# BLE_Shield_v1_0.net
KiCad netlist of a schematic drawn in EAGLE
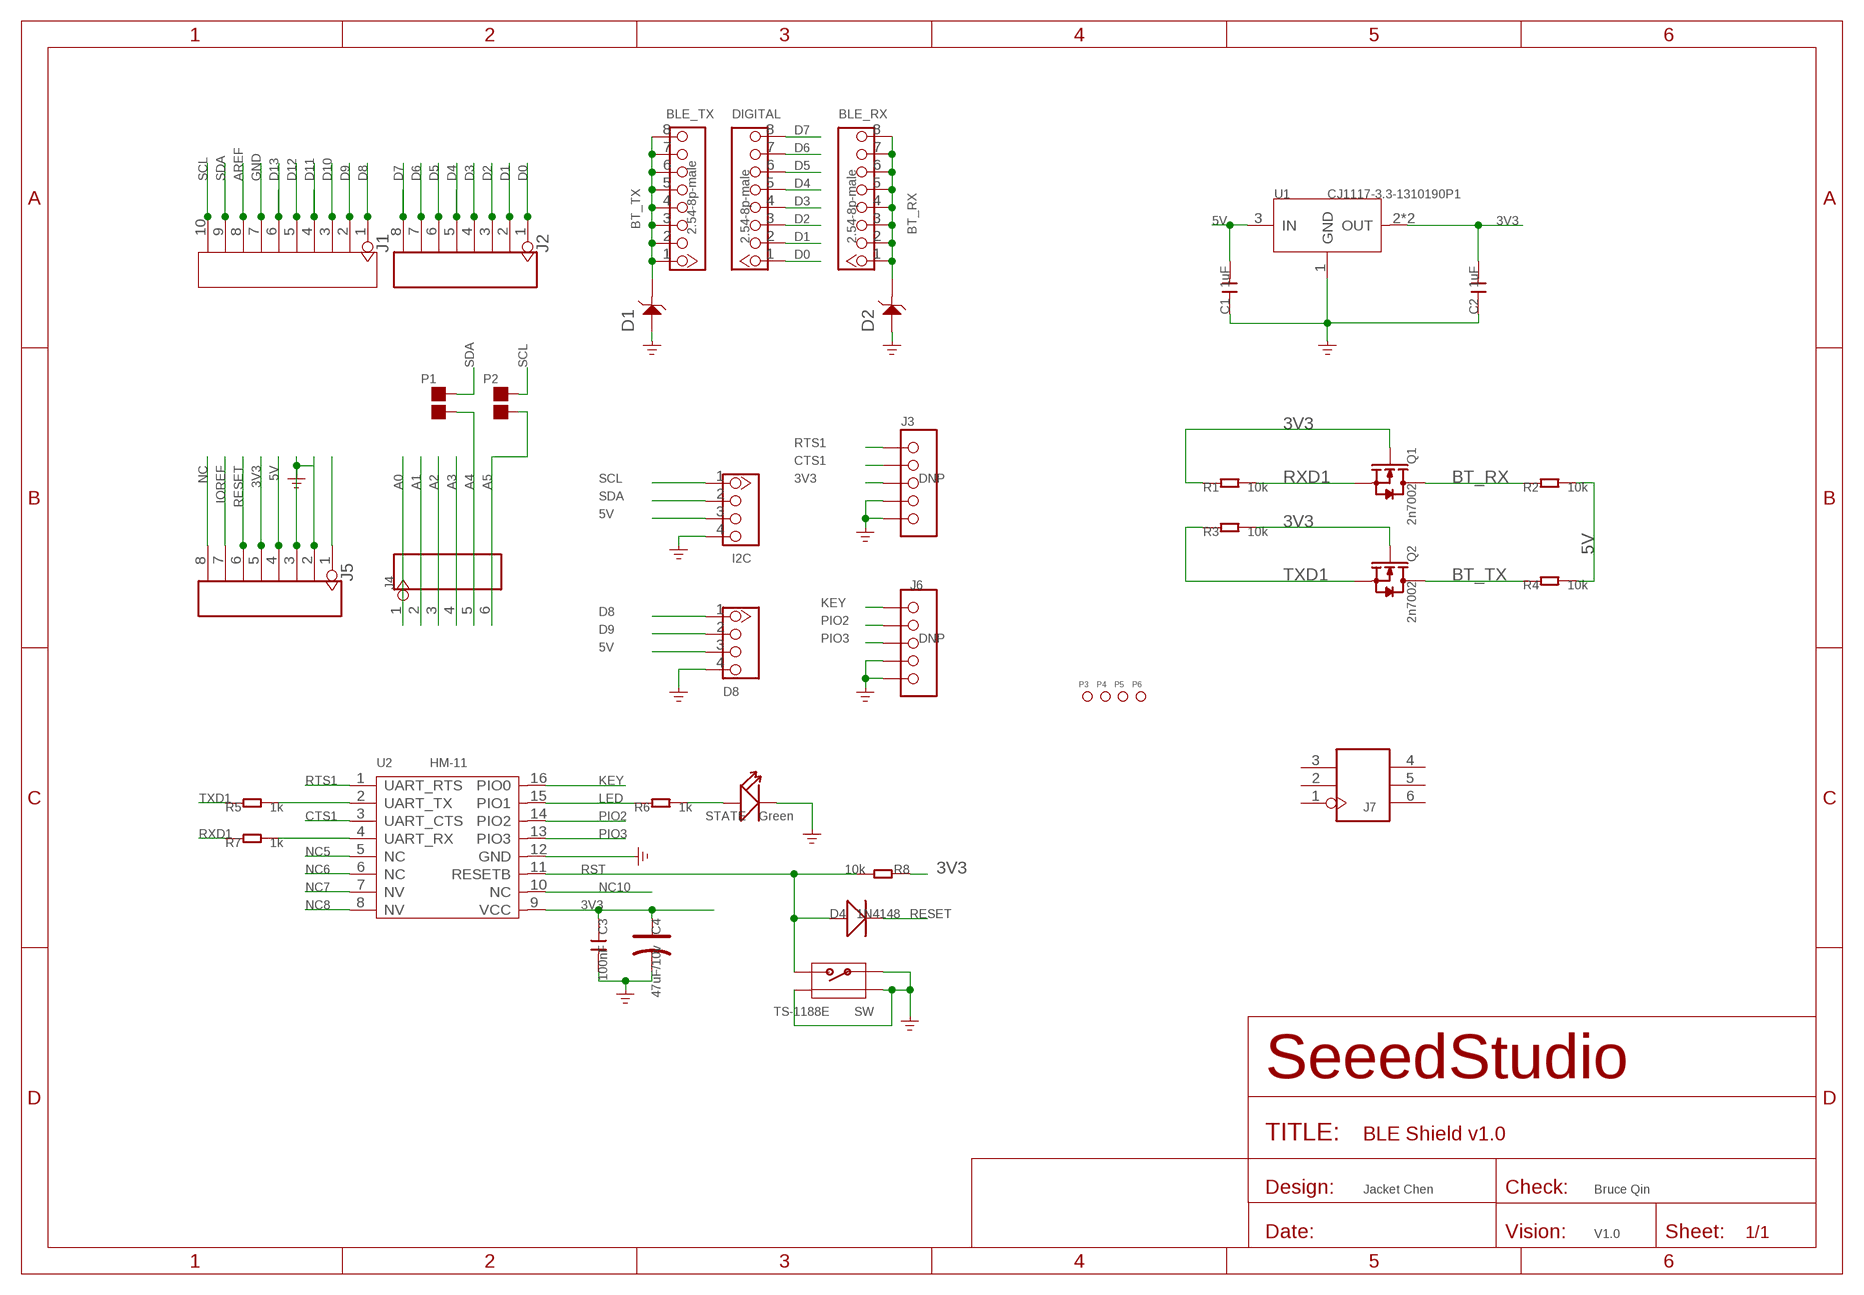
[diagram p0: schematic, sheet 1]

(export (version "E")
  (design (tool "Eeschema 10.0.6"))
  (components
    (comp (ref "BLE_RX")
      (value "2.54-8p-male")
      (footprint "eagle-import:8P-2.54")
      (libsource (lib "eagle-import") (part "HEADER-8P-2.54"))
    )
    (comp (ref "BLE_TX")
      (value "2.54-8p-male")
      (footprint "eagle-import:8P-2.54")
      (libsource (lib "eagle-import") (part "HEADER-8P-2.54"))
    )
    (comp (ref "C1")
      (value "1uF")
      (footprint "eagle-import:C0603")
      (libsource (lib "eagle-import") (part "C-0603"))
    )
    (comp (ref "C2")
      (value "1uF")
      (footprint "eagle-import:C0603")
      (libsource (lib "eagle-import") (part "C-0603"))
    )
    (comp (ref "C3")
      (value "100nF")
      (footprint "eagle-import:C0603")
      (libsource (lib "eagle-import") (part "C-0603"))
    )
    (comp (ref "C4")
      (value "47uF/10v")
      (footprint "eagle-import:AVX-A")
      (libsource (lib "eagle-import") (part "CAP-AVX-A"))
    )
    (comp (ref "D1")
      (value "6.2V/250mW")
      (footprint "eagle-import:SOD123-2.7X1.6")
      (libsource (lib "eagle-import") (part "D-ESD-2P'CESD5V0D1'"))
    )
    (comp (ref "D2")
      (value "6.2V/250mW")
      (footprint "eagle-import:SOD123-2.7X1.6")
      (libsource (lib "eagle-import") (part "D-ESD-2P'CESD5V0D1'"))
    )
    (comp (ref "D4")
      (value "1N4148")
      (footprint "eagle-import:LL-34")
      (libsource (lib "eagle-import") (part "D'1N4148-SMD'"))
    )
    (comp (ref "D8")
      (value "DIP Grove")
      (footprint "eagle-import:4P-2.0")
      (libsource (lib "eagle-import") (part "TWIG-4P-2.0-2.0"))
    )
    (comp (ref "DIGITAL")
      (value "2.54-8p-male")
      (footprint "eagle-import:8P-2.54")
      (libsource (lib "eagle-import") (part "HEADER-8P-2.54"))
    )
    (comp (ref "I2C")
      (value "DIP Grove")
      (footprint "eagle-import:4P-2.0")
      (libsource (lib "eagle-import") (part "TWIG-4P-2.0-2.0"))
    )
    (comp (ref "J1")
      (value "DIP Long Blue Female Header")
      (footprint "eagle-import:10P-2.54")
      (libsource (lib "eagle-import") (part "HEADER-10P-2.54"))
    )
    (comp (ref "J2")
      (value "DIP Long Blue Female Header")
      (footprint "eagle-import:8P-2.54-65_35MIL")
      (libsource (lib "eagle-import") (part "HEADER-8P-65/35MIL"))
    )
    (comp (ref "J3")
      (value "DNP")
      (footprint "eagle-import:5P-2.54")
      (libsource (lib "eagle-import") (part "HEADER-5P-2.54"))
    )
    (comp (ref "J4")
      (value "DIP Long Blue Female Header")
      (footprint "eagle-import:6P-2.54-65_35MIL")
      (libsource (lib "eagle-import") (part "HEADER-6P-65/35MIL"))
    )
    (comp (ref "J5")
      (value "DIP Long Blue Female Header")
      (footprint "eagle-import:8P-2.54-65_35MIL")
      (libsource (lib "eagle-import") (part "HEADER-8P-65/35MIL"))
    )
    (comp (ref "J6")
      (value "DNP")
      (footprint "eagle-import:5P-2.54")
      (libsource (lib "eagle-import") (part "HEADER-5P-2.54"))
    )
    (comp (ref "J7")
      (value "DIP Long Blue Female Header")
      (footprint "eagle-import:2X3P-2.54-65_35MIL")
      (libsource (lib "eagle-import") (part "HEADER-2X3P-65/35MIL"))
    )
    (comp (ref "P1")
      (value "DNP")
      (footprint "eagle-import:2P-SMD-1.78X1.27")
      (libsource (lib "eagle-import") (part "PAD-JUMPER-2P"))
    )
    (comp (ref "P2")
      (value "DNP")
      (footprint "eagle-import:2P-SMD-1.78X1.27")
      (libsource (lib "eagle-import") (part "PAD-JUMPER-2P"))
    )
    (comp (ref "P3")
      (value "PAD-MARK")
      (footprint "eagle-import:ROUND-MARK-1.0")
      (fields (field (name "PARTNO") "DNP"))
      (libsource (lib "eagle-import") (part "PAD-MARK"))
    )
    (comp (ref "P4")
      (value "PAD-MARK")
      (footprint "eagle-import:ROUND-MARK-1.0")
      (fields (field (name "PARTNO") "DNP"))
      (libsource (lib "eagle-import") (part "PAD-MARK"))
    )
    (comp (ref "P5")
      (value "PAD-MARK")
      (footprint "eagle-import:ROUND-MARK-1.0")
      (fields (field (name "PARTNO") "DNP"))
      (libsource (lib "eagle-import") (part "PAD-MARK"))
    )
    (comp (ref "P6")
      (value "PAD-MARK")
      (footprint "eagle-import:ROUND-MARK-1.0")
      (fields (field (name "PARTNO") "DNP"))
      (libsource (lib "eagle-import") (part "PAD-MARK"))
    )
    (comp (ref "Q1")
      (value "2n7002")
      (footprint "eagle-import:SOT23")
      (libsource (lib "eagle-import") (part "MOSFET-N'SOT23'"))
    )
    (comp (ref "Q2")
      (value "2n7002")
      (footprint "eagle-import:SOT23")
      (libsource (lib "eagle-import") (part "MOSFET-N'SOT23'"))
    )
    (comp (ref "R1")
      (value "10k")
      (footprint "eagle-import:R0603")
      (libsource (lib "eagle-import") (part "R-0603"))
    )
    (comp (ref "R2")
      (value "10k")
      (footprint "eagle-import:R0603")
      (libsource (lib "eagle-import") (part "R-0603"))
    )
    (comp (ref "R3")
      (value "10k")
      (footprint "eagle-import:R0603")
      (libsource (lib "eagle-import") (part "R-0603"))
    )
    (comp (ref "R4")
      (value "10k")
      (footprint "eagle-import:R0603")
      (libsource (lib "eagle-import") (part "R-0603"))
    )
    (comp (ref "R5")
      (value "1k")
      (footprint "eagle-import:R0603")
      (libsource (lib "eagle-import") (part "R-0603"))
    )
    (comp (ref "R6")
      (value "1k")
      (footprint "eagle-import:R0603")
      (libsource (lib "eagle-import") (part "R-0603"))
    )
    (comp (ref "R7")
      (value "1k")
      (footprint "eagle-import:R0603")
      (libsource (lib "eagle-import") (part "R-0603"))
    )
    (comp (ref "R8")
      (value "10k")
      (footprint "eagle-import:R0603")
      (libsource (lib "eagle-import") (part "R-0603"))
    )
    (comp (ref "STATE")
      (value "Green")
      (footprint "eagle-import:LED-0603")
      (libsource (lib "eagle-import") (part "LED'0603'"))
    )
    (comp (ref "SW")
      (value "TS-1188E")
      (footprint "eagle-import:4P-SMD-7X3.5X3.5H")
      (libsource (lib "eagle-import") (part "BUTTON-4P-REINFORCE'TS-1188E'"))
    )
    (comp (ref "U1")
      (value "CJ1117-3.3-1310190P1")
      (footprint "eagle-import:SOT223")
      (libsource (lib "eagle-import") (part "CJ1117-3.3-1310190P1"))
    )
    (comp (ref "U2")
      (value "HM-11")
      (footprint "eagle-import:16P-18.5X13.5X0.8")
      (libsource (lib "eagle-import") (part "HM-11"))
    )
  )
  (nets
    (net (code "1") (name "/3V3") (class "Default")
      (node (ref "C2") (pin "2") (pinfunction "2_2") (pintype "passive"))
      (node (ref "C3") (pin "1") (pinfunction "1_1") (pintype "passive"))
      (node (ref "C4") (pin "+") (pinfunction "+_+") (pintype "passive"))
      (node (ref "J3") (pin "3") (pinfunction "3_3") (pintype "bidirectional"))
      (node (ref "J5") (pin "5") (pinfunction "5_5") (pintype "bidirectional"))
      (node (ref "Q1") (pin "1") (pinfunction "G_1") (pintype "passive"))
      (node (ref "Q2") (pin "1") (pinfunction "G_1") (pintype "passive"))
      (node (ref "R1") (pin "1") (pinfunction "1_1") (pintype "passive"))
      (node (ref "R3") (pin "2") (pinfunction "2_2") (pintype "passive"))
      (node (ref "R8") (pin "1") (pinfunction "1_1") (pintype "passive"))
      (node (ref "U1") (pin "2") (pinfunction "OUT_2") (pintype "bidirectional"))
      (node (ref "U1") (pin "TER") (pinfunction "OUT_TER") (pintype "bidirectional"))
      (node (ref "U2") (pin "9") (pinfunction "VCC_9") (pintype "bidirectional"))
    )
    (net (code "2") (name "/5V") (class "Default")
      (node (ref "C1") (pin "2") (pinfunction "2_2") (pintype "passive"))
      (node (ref "D8") (pin "3") (pinfunction "3_3") (pintype "bidirectional"))
      (node (ref "I2C") (pin "3") (pinfunction "3_3") (pintype "bidirectional"))
      (node (ref "J5") (pin "4") (pinfunction "4_4") (pintype "bidirectional"))
      (node (ref "R2") (pin "2") (pinfunction "2_2") (pintype "passive"))
      (node (ref "R4") (pin "2") (pinfunction "2_2") (pintype "passive"))
      (node (ref "U1") (pin "3") (pinfunction "IN_3") (pintype "bidirectional"))
    )
    (net (code "3") (name "/A0") (class "Default")
      (node (ref "J4") (pin "1") (pinfunction "1_1") (pintype "bidirectional"))
    )
    (net (code "4") (name "/A1") (class "Default")
      (node (ref "J4") (pin "2") (pinfunction "2_2") (pintype "bidirectional"))
    )
    (net (code "5") (name "/A2") (class "Default")
      (node (ref "J4") (pin "3") (pinfunction "3_3") (pintype "bidirectional"))
    )
    (net (code "6") (name "/A3") (class "Default")
      (node (ref "J4") (pin "4") (pinfunction "4_4") (pintype "bidirectional"))
    )
    (net (code "7") (name "/A4") (class "Default")
      (node (ref "J4") (pin "5") (pinfunction "5_5") (pintype "bidirectional"))
      (node (ref "P1") (pin "1") (pinfunction "1_1") (pintype "bidirectional"))
    )
    (net (code "8") (name "/A5") (class "Default")
      (node (ref "J4") (pin "6") (pinfunction "6_6") (pintype "bidirectional"))
      (node (ref "P2") (pin "1") (pinfunction "1_1") (pintype "bidirectional"))
    )
    (net (code "9") (name "/AREF") (class "Default")
      (node (ref "J1") (pin "8") (pinfunction "8_8") (pintype "bidirectional"))
    )
    (net (code "10") (name "/BT_RX") (class "Default")
      (node (ref "BLE_RX") (pin "1") (pinfunction "1_1") (pintype "bidirectional"))
      (node (ref "BLE_RX") (pin "2") (pinfunction "2_2") (pintype "bidirectional"))
      (node (ref "BLE_RX") (pin "3") (pinfunction "3_3") (pintype "bidirectional"))
      (node (ref "BLE_RX") (pin "4") (pinfunction "4_4") (pintype "bidirectional"))
      (node (ref "BLE_RX") (pin "5") (pinfunction "5_5") (pintype "bidirectional"))
      (node (ref "BLE_RX") (pin "6") (pinfunction "6_6") (pintype "bidirectional"))
      (node (ref "BLE_RX") (pin "7") (pinfunction "7_7") (pintype "bidirectional"))
      (node (ref "BLE_RX") (pin "8") (pinfunction "8_8") (pintype "bidirectional"))
      (node (ref "D2") (pin "2") (pinfunction "2_2") (pintype "bidirectional"))
      (node (ref "Q1") (pin "3") (pinfunction "D_3") (pintype "passive"))
      (node (ref "R2") (pin "1") (pinfunction "1_1") (pintype "passive"))
    )
    (net (code "11") (name "/BT_TX") (class "Default")
      (node (ref "BLE_TX") (pin "1") (pinfunction "1_1") (pintype "bidirectional"))
      (node (ref "BLE_TX") (pin "2") (pinfunction "2_2") (pintype "bidirectional"))
      (node (ref "BLE_TX") (pin "3") (pinfunction "3_3") (pintype "bidirectional"))
      (node (ref "BLE_TX") (pin "4") (pinfunction "4_4") (pintype "bidirectional"))
      (node (ref "BLE_TX") (pin "5") (pinfunction "5_5") (pintype "bidirectional"))
      (node (ref "BLE_TX") (pin "6") (pinfunction "6_6") (pintype "bidirectional"))
      (node (ref "BLE_TX") (pin "7") (pinfunction "7_7") (pintype "bidirectional"))
      (node (ref "BLE_TX") (pin "8") (pinfunction "8_8") (pintype "bidirectional"))
      (node (ref "D1") (pin "2") (pinfunction "2_2") (pintype "bidirectional"))
      (node (ref "Q2") (pin "3") (pinfunction "D_3") (pintype "passive"))
      (node (ref "R4") (pin "1") (pinfunction "1_1") (pintype "passive"))
    )
    (net (code "12") (name "/CTS1") (class "Default")
      (node (ref "J3") (pin "2") (pinfunction "2_2") (pintype "bidirectional"))
      (node (ref "U2") (pin "3") (pinfunction "UART_CTS_3") (pintype "bidirectional"))
    )
    (net (code "13") (name "/D0") (class "Default")
      (node (ref "DIGITAL") (pin "1") (pinfunction "1_1") (pintype "bidirectional"))
      (node (ref "J2") (pin "1") (pinfunction "1_1") (pintype "bidirectional"))
    )
    (net (code "14") (name "/D1") (class "Default")
      (node (ref "DIGITAL") (pin "2") (pinfunction "2_2") (pintype "bidirectional"))
      (node (ref "J2") (pin "2") (pinfunction "2_2") (pintype "bidirectional"))
    )
    (net (code "15") (name "/D2") (class "Default")
      (node (ref "DIGITAL") (pin "3") (pinfunction "3_3") (pintype "bidirectional"))
      (node (ref "J2") (pin "3") (pinfunction "3_3") (pintype "bidirectional"))
    )
    (net (code "16") (name "/D3") (class "Default")
      (node (ref "DIGITAL") (pin "4") (pinfunction "4_4") (pintype "bidirectional"))
      (node (ref "J2") (pin "4") (pinfunction "4_4") (pintype "bidirectional"))
    )
    (net (code "17") (name "/D4") (class "Default")
      (node (ref "DIGITAL") (pin "5") (pinfunction "5_5") (pintype "bidirectional"))
      (node (ref "J2") (pin "5") (pinfunction "5_5") (pintype "bidirectional"))
    )
    (net (code "18") (name "/D5") (class "Default")
      (node (ref "DIGITAL") (pin "6") (pinfunction "6_6") (pintype "bidirectional"))
      (node (ref "J2") (pin "6") (pinfunction "6_6") (pintype "bidirectional"))
    )
    (net (code "19") (name "/D6") (class "Default")
      (node (ref "DIGITAL") (pin "7") (pinfunction "7_7") (pintype "bidirectional"))
      (node (ref "J2") (pin "7") (pinfunction "7_7") (pintype "bidirectional"))
    )
    (net (code "20") (name "/D7") (class "Default")
      (node (ref "DIGITAL") (pin "8") (pinfunction "8_8") (pintype "bidirectional"))
      (node (ref "J2") (pin "8") (pinfunction "8_8") (pintype "bidirectional"))
    )
    (net (code "21") (name "/D8") (class "Default")
      (node (ref "D8") (pin "1") (pinfunction "1_1") (pintype "bidirectional"))
      (node (ref "J1") (pin "1") (pinfunction "1_1") (pintype "bidirectional"))
    )
    (net (code "22") (name "/D9") (class "Default")
      (node (ref "D8") (pin "2") (pinfunction "2_2") (pintype "bidirectional"))
      (node (ref "J1") (pin "2") (pinfunction "2_2") (pintype "bidirectional"))
    )
    (net (code "23") (name "/D10") (class "Default")
      (node (ref "J1") (pin "3") (pinfunction "3_3") (pintype "bidirectional"))
    )
    (net (code "24") (name "/D11") (class "Default")
      (node (ref "J1") (pin "4") (pinfunction "4_4") (pintype "bidirectional"))
    )
    (net (code "25") (name "/D12") (class "Default")
      (node (ref "J1") (pin "5") (pinfunction "5_5") (pintype "bidirectional"))
    )
    (net (code "26") (name "/D13") (class "Default")
      (node (ref "J1") (pin "6") (pinfunction "6_6") (pintype "bidirectional"))
    )
    (net (code "27") (name "/IOREF") (class "Default")
      (node (ref "J5") (pin "7") (pinfunction "7_7") (pintype "bidirectional"))
    )
    (net (code "28") (name "/KEY") (class "Default")
      (node (ref "J6") (pin "1") (pinfunction "1_1") (pintype "bidirectional"))
      (node (ref "U2") (pin "16") (pinfunction "PIO0_16") (pintype "bidirectional"))
    )
    (net (code "29") (name "/LED") (class "Default")
      (node (ref "R6") (pin "1") (pinfunction "1_1") (pintype "passive"))
      (node (ref "U2") (pin "15") (pinfunction "PIO1_15") (pintype "bidirectional"))
    )
    (net (code "30") (name "/NC") (class "Default")
      (node (ref "J5") (pin "8") (pinfunction "8_8") (pintype "bidirectional"))
    )
    (net (code "31") (name "/NC5") (class "Default")
      (node (ref "U2") (pin "5") (pinfunction "NC_5") (pintype "bidirectional"))
    )
    (net (code "32") (name "/NC6") (class "Default")
      (node (ref "U2") (pin "6") (pinfunction "NC_6") (pintype "bidirectional"))
    )
    (net (code "33") (name "/NC7") (class "Default")
      (node (ref "U2") (pin "7") (pinfunction "NV_7") (pintype "bidirectional"))
    )
    (net (code "34") (name "/NC8") (class "Default")
      (node (ref "U2") (pin "8") (pinfunction "NV_8") (pintype "bidirectional"))
    )
    (net (code "35") (name "/NC10") (class "Default")
      (node (ref "U2") (pin "10") (pinfunction "NC_10") (pintype "bidirectional"))
    )
    (net (code "36") (name "/PIO2") (class "Default")
      (node (ref "J6") (pin "2") (pinfunction "2_2") (pintype "bidirectional"))
      (node (ref "U2") (pin "14") (pinfunction "PIO2_14") (pintype "bidirectional"))
    )
    (net (code "37") (name "/PIO3") (class "Default")
      (node (ref "J6") (pin "3") (pinfunction "3_3") (pintype "bidirectional"))
      (node (ref "U2") (pin "13") (pinfunction "PIO3_13") (pintype "bidirectional"))
    )
    (net (code "38") (name "/RESET") (class "Default")
      (node (ref "D4") (pin "C") (pinfunction "-_C") (pintype "passive"))
      (node (ref "J5") (pin "6") (pinfunction "6_6") (pintype "bidirectional"))
    )
    (net (code "39") (name "/RST") (class "Default")
      (node (ref "D4") (pin "A") (pinfunction "+_A") (pintype "passive"))
      (node (ref "R8") (pin "2") (pinfunction "2_2") (pintype "passive"))
      (node (ref "SW") (pin "2") (pinfunction "2_2") (pintype "bidirectional"))
      (node (ref "U2") (pin "11") (pinfunction "RESETB_11") (pintype "bidirectional"))
    )
    (net (code "40") (name "/RTS1") (class "Default")
      (node (ref "J3") (pin "1") (pinfunction "1_1") (pintype "bidirectional"))
      (node (ref "U2") (pin "1") (pinfunction "UART_RTS_1") (pintype "bidirectional"))
    )
    (net (code "41") (name "/RXD1") (class "Default")
      (node (ref "Q1") (pin "2") (pinfunction "S_2") (pintype "passive"))
      (node (ref "R1") (pin "2") (pinfunction "2_2") (pintype "passive"))
      (node (ref "R7") (pin "1") (pinfunction "1_1") (pintype "passive"))
    )
    (net (code "42") (name "/SCL") (class "Default")
      (node (ref "I2C") (pin "1") (pinfunction "1_1") (pintype "bidirectional"))
      (node (ref "J1") (pin "10") (pinfunction "10_10") (pintype "bidirectional"))
      (node (ref "P2") (pin "2") (pinfunction "2_2") (pintype "bidirectional"))
    )
    (net (code "43") (name "/SDA") (class "Default")
      (node (ref "I2C") (pin "2") (pinfunction "2_2") (pintype "bidirectional"))
      (node (ref "J1") (pin "9") (pinfunction "9_9") (pintype "bidirectional"))
      (node (ref "P1") (pin "2") (pinfunction "2_2") (pintype "bidirectional"))
    )
    (net (code "44") (name "/TXD1") (class "Default")
      (node (ref "Q2") (pin "2") (pinfunction "S_2") (pintype "passive"))
      (node (ref "R3") (pin "1") (pinfunction "1_1") (pintype "passive"))
      (node (ref "R5") (pin "1") (pinfunction "1_1") (pintype "passive"))
    )
    (net (code "45") (name "GND") (class "Default")
      (node (ref "C1") (pin "1") (pinfunction "1_1") (pintype "passive"))
      (node (ref "C2") (pin "1") (pinfunction "1_1") (pintype "passive"))
      (node (ref "C3") (pin "2") (pinfunction "2_2") (pintype "passive"))
      (node (ref "C4") (pin "-") (pinfunction "-_-") (pintype "passive"))
      (node (ref "D1") (pin "1") (pinfunction "1_1") (pintype "bidirectional"))
      (node (ref "D2") (pin "1") (pinfunction "1_1") (pintype "bidirectional"))
      (node (ref "D8") (pin "4") (pinfunction "4_4") (pintype "bidirectional"))
      (node (ref "I2C") (pin "4") (pinfunction "4_4") (pintype "bidirectional"))
      (node (ref "J1") (pin "7") (pinfunction "7_7") (pintype "bidirectional"))
      (node (ref "J3") (pin "4") (pinfunction "4_4") (pintype "bidirectional"))
      (node (ref "J3") (pin "5") (pinfunction "5_5") (pintype "bidirectional"))
      (node (ref "J5") (pin "2") (pinfunction "2_2") (pintype "bidirectional"))
      (node (ref "J5") (pin "3") (pinfunction "3_3") (pintype "bidirectional"))
      (node (ref "J6") (pin "4") (pinfunction "4_4") (pintype "bidirectional"))
      (node (ref "J6") (pin "5") (pinfunction "5_5") (pintype "bidirectional"))
      (node (ref "STATE") (pin "-") (pinfunction "-_-") (pintype "passive"))
      (node (ref "SW") (pin "1") (pinfunction "1_1") (pintype "bidirectional"))
      (node (ref "SW") (pin "S1") (pinfunction "S1_S1") (pintype "bidirectional"))
      (node (ref "SW") (pin "S2") (pinfunction "S2_S2") (pintype "bidirectional"))
      (node (ref "U1") (pin "1") (pinfunction "GND_1") (pintype "bidirectional"))
      (node (ref "U2") (pin "12") (pinfunction "GND_12") (pintype "bidirectional"))
    )
    (net (code "46") (name "Net-(R6-Pad2)") (class "Default")
      (node (ref "R6") (pin "2") (pinfunction "2_2") (pintype "passive"))
      (node (ref "STATE") (pin "+") (pinfunction "+_+") (pintype "passive"))
    )
    (net (code "47") (name "Net-(U2-UART_RX)") (class "Default")
      (node (ref "R7") (pin "2") (pinfunction "2_2") (pintype "passive"))
      (node (ref "U2") (pin "4") (pinfunction "UART_RX_4") (pintype "bidirectional"))
    )
    (net (code "48") (name "Net-(U2-UART_TX)") (class "Default")
      (node (ref "R5") (pin "2") (pinfunction "2_2") (pintype "passive"))
      (node (ref "U2") (pin "2") (pinfunction "UART_TX_2") (pintype "bidirectional"))
    )
    (net (code "49") (name "unconnected-(J5-Pad1)") (class "Default")
      (node (ref "J5") (pin "1") (pinfunction "1_1") (pintype "bidirectional"))
    )
    (net (code "50") (name "unconnected-(J7-Pad1)") (class "Default")
      (node (ref "J7") (pin "1") (pinfunction "1_1") (pintype "bidirectional"))
    )
    (net (code "51") (name "unconnected-(J7-Pad2)") (class "Default")
      (node (ref "J7") (pin "2") (pinfunction "2_2") (pintype "bidirectional"))
    )
    (net (code "52") (name "unconnected-(J7-Pad3)") (class "Default")
      (node (ref "J7") (pin "3") (pinfunction "3_3") (pintype "bidirectional"))
    )
    (net (code "53") (name "unconnected-(J7-Pad4)") (class "Default")
      (node (ref "J7") (pin "4") (pinfunction "4_4") (pintype "bidirectional"))
    )
    (net (code "54") (name "unconnected-(J7-Pad5)") (class "Default")
      (node (ref "J7") (pin "5") (pinfunction "5_5") (pintype "bidirectional"))
    )
    (net (code "55") (name "unconnected-(J7-Pad6)") (class "Default")
      (node (ref "J7") (pin "6") (pinfunction "6_6") (pintype "bidirectional"))
    )
  )
)
